# ISL6236A_DEMO.net
KiCad netlist of a schematic drawn in Altium Designer
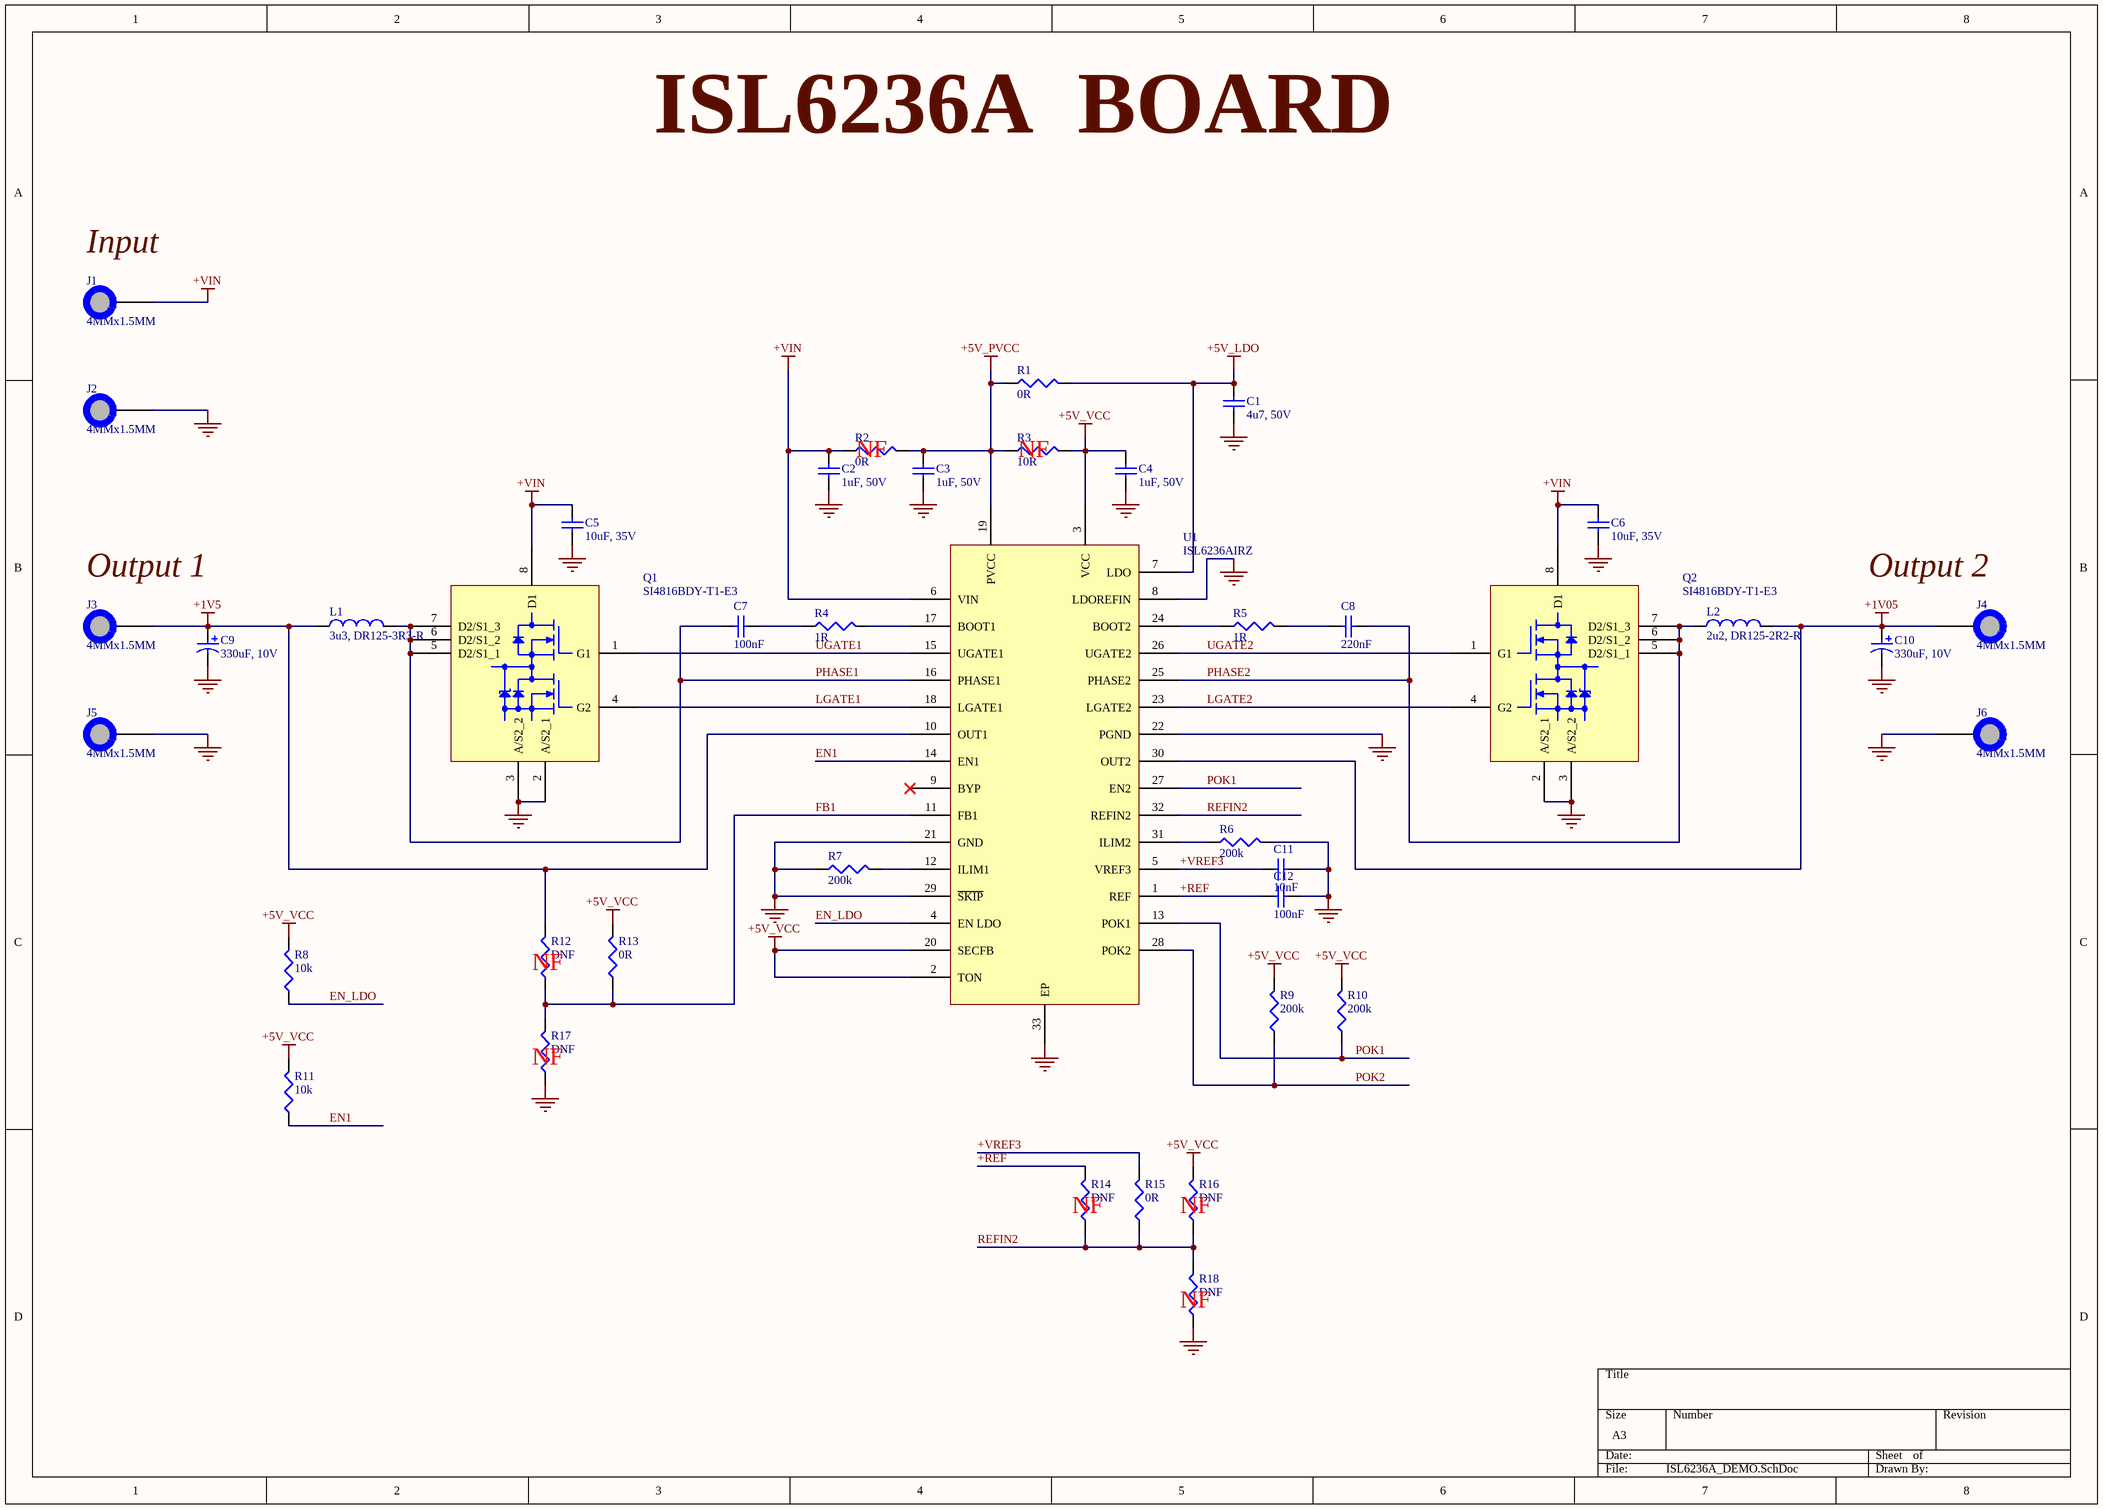
[diagram p0: ISL6236A_DEMO.SchDoc]

(export (version "E")
  (design (tool "Eeschema 10.0.6"))
  (components
    (comp (ref "C1")
      (value "4u7, 50V")
      (footprint "C1206")
      (description "CAP CER 4.7UF 50V X5R 1206")
      (fields
        (field (name "MANUFACTURER") "TDK")
        (field (name "MANUFACTURER PART NUMBER") "C3216X5R1H475K160AB")
      )
      (libsource (lib "ISL6236A_DEMO") (part "C3216X5R1H475K160AB"))
    )
    (comp (ref "C2")
      (value "1uF, 50V")
      (footprint "C0805")
      (description "Multilayer Ceramic Capacitors MLCC - SMD/SMT 1uF 50 Volts 10% X7R")
      (fields
        (field (name "MANUFACTURER") "KEMET")
        (field (name "MANUFACTURER PART NUMBER") "C0805C105K5RACTU")
      )
      (libsource (lib "ISL6236A_DEMO") (part "C0805C105K5RACTU"))
    )
    (comp (ref "C3")
      (value "1uF, 50V")
      (footprint "C0805")
      (description "Multilayer Ceramic Capacitors MLCC - SMD/SMT 1uF 50 Volts 10% X7R")
      (fields
        (field (name "MANUFACTURER") "KEMET")
        (field (name "MANUFACTURER PART NUMBER") "C0805C105K5RACTU")
      )
      (libsource (lib "ISL6236A_DEMO") (part "C0805C105K5RACTU"))
    )
    (comp (ref "C4")
      (value "1uF, 50V")
      (footprint "C0805")
      (description "Multilayer Ceramic Capacitors MLCC - SMD/SMT 1uF 50 Volts 10% X7R")
      (fields
        (field (name "MANUFACTURER") "KEMET")
        (field (name "MANUFACTURER PART NUMBER") "C0805C105K5RACTU")
      )
      (libsource (lib "ISL6236A_DEMO") (part "C0805C105K5RACTU"))
    )
    (comp (ref "C5")
      (value "10uF, 35V")
      (footprint "C1210")
      (description "1210 C 10uF Ceramic Multilayer Capacitor,  35 VDC,  +85degC,  X5R Dielec,  +/-10%")
      (fields
        (field (name "MANUFACTURER") "KEMET")
        (field (name "MANUFACTURER PART NUMBER") "C1210C106K6PACTU")
      )
      (libsource (lib "ISL6236A_DEMO") (part "C1210C106K6PACTU"))
    )
    (comp (ref "C6")
      (value "10uF, 35V")
      (footprint "C1210")
      (description "1210 C 10uF Ceramic Multilayer Capacitor,  35 VDC,  +85degC,  X5R Dielec,  +/-10%")
      (fields
        (field (name "MANUFACTURER") "KEMET")
        (field (name "MANUFACTURER PART NUMBER") "C1210C106K6PACTU")
      )
      (libsource (lib "ISL6236A_DEMO") (part "C1210C106K6PACTU"))
    )
    (comp (ref "C7")
      (value "100nF")
      (footprint "C0805")
      (description "Multilayer Ceramic Capacitors MLCC - SMD/SMT 50volts 0.1uF X7R 10%")
      (fields
        (field (name "MANUFACTURER") "KEMET")
        (field (name "MANUFACTURER PART NUMBER") "C0805C104K5RAC7800")
      )
      (libsource (lib "ISL6236A_DEMO") (part "C0805C104K5RAC7800"))
    )
    (comp (ref "C8")
      (value "220nF")
      (footprint "C0805")
      (description "CAP CER 0.22UF 50V X7R 0805")
      (fields
        (field (name "MANUFACTURER") "KEMET")
        (field (name "MANUFACTURER PART NUMBER") "C0805C224K5RACTU")
      )
      (libsource (lib "ISL6236A_DEMO") (part "C0805C224K5RACTU"))
    )
    (comp (ref "C9")
      (value "330uF, 10V")
      (footprint "7343-43")
      (description "Tantalum Capacitors - Polymer SMD 330uF 10volts 20%")
      (fields
        (field (name "MANUFACTURER") "KEMET")
        (field (name "MANUFACTURER PART NUMBER") "T530X337M010ATE004")
      )
      (libsource (lib "ISL6236A_DEMO") (part "T530X337M010ATE004"))
    )
    (comp (ref "C10")
      (value "330uF, 10V")
      (footprint "7343-43")
      (description "Tantalum Capacitors - Polymer SMD 330uF 10volts 20%")
      (fields
        (field (name "MANUFACTURER") "KEMET")
        (field (name "MANUFACTURER PART NUMBER") "T530X337M010ATE004")
      )
      (libsource (lib "ISL6236A_DEMO") (part "T530X337M010ATE004"))
    )
    (comp (ref "C11")
      (value "10nF")
      (footprint "C0805")
      (description "CAP CER 10000PF 50V X7R 0805")
      (fields
        (field (name "MANUFACTURER") "KEMET")
        (field (name "MANUFACTURER PART NUMBER") "C0805F103K5RACTU")
      )
      (libsource (lib "ISL6236A_DEMO") (part "C0805F103K5RACTU"))
    )
    (comp (ref "C12")
      (value "100nF")
      (footprint "C0805")
      (description "Multilayer Ceramic Capacitors MLCC - SMD/SMT 50volts 0.1uF X7R 10%")
      (fields
        (field (name "MANUFACTURER") "KEMET")
        (field (name "MANUFACTURER PART NUMBER") "C0805C104K5RAC7800")
      )
      (libsource (lib "ISL6236A_DEMO") (part "C0805C104K5RAC7800"))
    )
    (comp (ref "J1")
      (value "4MMx1.5MM")
      (footprint "PAD_WITH_HOLE_4MMx1MM5")
      (description "Pad with a hole 4mm x 1.5mm")
      (libsource (lib "ISL6236A_DEMO") (part "PAD_WITH_HOLE_4MMx1MM5"))
    )
    (comp (ref "J2")
      (value "4MMx1.5MM")
      (footprint "PAD_WITH_HOLE_4MMx1MM5")
      (description "Pad with a hole 4mm x 1.5mm")
      (libsource (lib "ISL6236A_DEMO") (part "PAD_WITH_HOLE_4MMx1MM5"))
    )
    (comp (ref "J3")
      (value "4MMx1.5MM")
      (footprint "PAD_WITH_HOLE_4MMx1MM5")
      (description "Pad with a hole 4mm x 1.5mm")
      (libsource (lib "ISL6236A_DEMO") (part "PAD_WITH_HOLE_4MMx1MM5"))
    )
    (comp (ref "J4")
      (value "4MMx1.5MM")
      (footprint "PAD_WITH_HOLE_4MMx1MM5")
      (description "Pad with a hole 4mm x 1.5mm")
      (libsource (lib "ISL6236A_DEMO") (part "PAD_WITH_HOLE_4MMx1MM5"))
    )
    (comp (ref "J5")
      (value "4MMx1.5MM")
      (footprint "PAD_WITH_HOLE_4MMx1MM5")
      (description "Pad with a hole 4mm x 1.5mm")
      (libsource (lib "ISL6236A_DEMO") (part "PAD_WITH_HOLE_4MMx1MM5"))
    )
    (comp (ref "J6")
      (value "4MMx1.5MM")
      (footprint "PAD_WITH_HOLE_4MMx1MM5")
      (description "Pad with a hole 4mm x 1.5mm")
      (libsource (lib "ISL6236A_DEMO") (part "PAD_WITH_HOLE_4MMx1MM5"))
    )
    (comp (ref "L1")
      (value "3u3, DR125-3R3-R")
      (footprint "DR125")
      (description "Inductor Power Shielded Drum Core 3.084uH/3.3uH 20% 100KHz Ferrite 9.26A 6.3mOhm DCR T/R")
      (fields
        (field (name "MANUFACTURER") "Eaton Cooper")
        (field (name "MANUFACTURER PART NUMBER") "DR125-3R3-R")
      )
      (libsource (lib "ISL6236A_DEMO") (part "DR125-3R3-R"))
    )
    (comp (ref "L2")
      (value "2u2, DR125-2R2-R")
      (footprint "DR125")
      (description "Fixed Inductors 2.2uH 15A 0.0045ohms")
      (fields
        (field (name "MANUFACTURER") "Eaton Cooper")
        (field (name "MANUFACTURER PART NUMBER") "DR125-2R2-R")
      )
      (libsource (lib "ISL6236A_DEMO") (part "DR125-2R2-R"))
    )
    (comp (ref "Q1")
      (value "SI4816BDY-T1-E3")
      (footprint "SO-8")
      (description "MOSFET 2N-CH 30V 5.8A 8-SOIC")
      (fields (field (name "MANUFACTURER") "Vishay Siliconix"))
      (libsource (lib "ISL6236A_DEMO") (part "SI4816BDY-T1-E3"))
    )
    (comp (ref "Q2")
      (value "SI4816BDY-T1-E3")
      (footprint "SO-8")
      (description "MOSFET 2N-CH 30V 5.8A 8-SOIC")
      (fields (field (name "MANUFACTURER") "Vishay Siliconix"))
      (libsource (lib "") (part "SI4816BDY-T1-E3_1"))
    )
    (comp (ref "R1")
      (value "0R")
      (footprint "R0805")
      (description "Thick Film Resistors - SMD 1/8W 0.0ohm 5%")
      (fields
        (field (name "MANUFACTURER") "Yageo")
        (field (name "MANUFACTURER PART NUMBER") "AC0805JR-070RL")
      )
      (libsource (lib "ISL6236A_DEMO") (part "AC0805JR-070RL"))
    )
    (comp (ref "R2")
      (value "0R")
      (footprint "R0805")
      (description "Thick Film Resistors - SMD 1/8W 0.0ohm 5%")
      (fields
        (field (name "MANUFACTURER") "Yageo")
        (field (name "MANUFACTURER PART NUMBER") "AC0805JR-070RL")
      )
      (libsource (lib "ISL6236A_DEMO") (part "AC0805JR-070RL"))
    )
    (comp (ref "R3")
      (value "10R")
      (footprint "R0805")
      (description "Thick Film Resistors - SMD 1/8W 10ohm 1%")
      (fields
        (field (name "MANUFACTURER") "Yageo")
        (field (name "MANUFACTURER PART NUMBER") "AC0805FR-0710RL")
      )
      (libsource (lib "ISL6236A_DEMO") (part "AC0805FR-0710RL"))
    )
    (comp (ref "R4")
      (value "1R")
      (footprint "R0805")
      (description "Thick Film Resistors - SMD 1/8W 1ohm 1% AEC-Q200")
      (fields
        (field (name "MANUFACTURER") "Yageo")
        (field (name "MANUFACTURER PART NUMBER") "AC0805FR-071RL")
      )
      (libsource (lib "ISL6236A_DEMO") (part "AC0805FR-071RL"))
    )
    (comp (ref "R5")
      (value "1R")
      (footprint "R0805")
      (description "Thick Film Resistors - SMD 1/8W 1ohm 1% AEC-Q200")
      (fields
        (field (name "MANUFACTURER") "Yageo")
        (field (name "MANUFACTURER PART NUMBER") "AC0805FR-071RL")
      )
      (libsource (lib "ISL6236A_DEMO") (part "AC0805FR-071RL"))
    )
    (comp (ref "R6")
      (value "200k")
      (footprint "R0805")
      (description "Thick Film Resistors - SMD 1/8W 200K ohm 1%")
      (fields
        (field (name "MANUFACTURER") "Yageo")
        (field (name "MANUFACTURER PART NUMBER") "AC0805FR-07200KL")
      )
      (libsource (lib "ISL6236A_DEMO") (part "AC0805FR-07200KL"))
    )
    (comp (ref "R7")
      (value "200k")
      (footprint "R0805")
      (description "Thick Film Resistors - SMD 1/8W 200K ohm 1%")
      (fields
        (field (name "MANUFACTURER") "Yageo")
        (field (name "MANUFACTURER PART NUMBER") "AC0805FR-07200KL")
      )
      (libsource (lib "ISL6236A_DEMO") (part "AC0805FR-07200KL"))
    )
    (comp (ref "R8")
      (value "10k")
      (footprint "R0805")
      (description "RES SMD 10K OHM 1% 1/8W 0805")
      (fields
        (field (name "MANUFACTURER") "Yageo")
        (field (name "MANUFACTURER PART NUMBER") "AC0805FR-0710KL")
      )
      (libsource (lib "ISL6236A_DEMO") (part "AC0805FR-0710KL"))
    )
    (comp (ref "R9")
      (value "200k")
      (footprint "R0805")
      (description "Thick Film Resistors - SMD 1/8W 200K ohm 1%")
      (fields
        (field (name "MANUFACTURER") "Yageo")
        (field (name "MANUFACTURER PART NUMBER") "AC0805FR-07200KL")
      )
      (libsource (lib "ISL6236A_DEMO") (part "AC0805FR-07200KL"))
    )
    (comp (ref "R10")
      (value "200k")
      (footprint "R0805")
      (description "Thick Film Resistors - SMD 1/8W 200K ohm 1%")
      (fields
        (field (name "MANUFACTURER") "Yageo")
        (field (name "MANUFACTURER PART NUMBER") "AC0805FR-07200KL")
      )
      (libsource (lib "ISL6236A_DEMO") (part "AC0805FR-07200KL"))
    )
    (comp (ref "R11")
      (value "10k")
      (footprint "R0805")
      (description "RES SMD 10K OHM 1% 1/8W 0805")
      (fields
        (field (name "MANUFACTURER") "Yageo")
        (field (name "MANUFACTURER PART NUMBER") "AC0805FR-0710KL")
      )
      (libsource (lib "ISL6236A_DEMO") (part "AC0805FR-0710KL"))
    )
    (comp (ref "R12") (value "DNF") (footprint "R0805") (libsource (lib "ISL6236A_DEMO") (part "RES")))
    (comp (ref "R13")
      (value "0R")
      (footprint "R0805")
      (description "Thick Film Resistors - SMD 1/8W 0.0ohm 5%")
      (fields
        (field (name "MANUFACTURER") "Yageo")
        (field (name "MANUFACTURER PART NUMBER") "AC0805JR-070RL")
      )
      (libsource (lib "ISL6236A_DEMO") (part "AC0805JR-070RL"))
    )
    (comp (ref "R14") (value "DNF") (footprint "R0805") (libsource (lib "ISL6236A_DEMO") (part "RES")))
    (comp (ref "R15")
      (value "0R")
      (footprint "R0805")
      (description "Thick Film Resistors - SMD 1/8W 0.0ohm 5%")
      (fields
        (field (name "MANUFACTURER") "Yageo")
        (field (name "MANUFACTURER PART NUMBER") "AC0805JR-070RL")
      )
      (libsource (lib "ISL6236A_DEMO") (part "AC0805JR-070RL"))
    )
    (comp (ref "R16") (value "DNF") (footprint "R0805") (libsource (lib "ISL6236A_DEMO") (part "RES")))
    (comp (ref "R17") (value "DNF") (footprint "R0805") (libsource (lib "ISL6236A_DEMO") (part "RES")))
    (comp (ref "R18") (value "DNF") (footprint "R0805") (libsource (lib "ISL6236A_DEMO") (part "RES")))
    (comp (ref "U1")
      (value "ISL6236AIRZ")
      (footprint "L32.5x5B")
      (description "IC MAIN PWR CTRLR QUAD 32-QFN")
      (fields (field (name "MANUFACTURER") "Intersil"))
      (libsource (lib "ISL6236A_DEMO") (part "ISL6236AIRZ"))
    )
  )
  (nets
    (net (code "1") (name "+1V5") (class "Default")
      (node (ref "C9") (pin "1") (pinfunction "1_1") (pintype "passive"))
      (node (ref "J3") (pin "1") (pinfunction "1_1") (pintype "passive"))
      (node (ref "L1") (pin "1") (pinfunction "1_1") (pintype "passive"))
      (node (ref "R12") (pin "2") (pinfunction "2_2") (pintype "passive"))
      (node (ref "U1") (pin "10") (pinfunction "OUT1_10") (pintype "passive"))
    )
    (net (code "2") (name "+1V05") (class "Default")
      (node (ref "C10") (pin "1") (pinfunction "1_1") (pintype "passive"))
      (node (ref "J4") (pin "1") (pinfunction "1_1") (pintype "passive"))
      (node (ref "L2") (pin "2") (pinfunction "2_2") (pintype "passive"))
      (node (ref "U1") (pin "30") (pinfunction "OUT2_30") (pintype "passive"))
    )
    (net (code "3") (name "+5V_LDO") (class "Default")
      (node (ref "C1") (pin "2") (pinfunction "2_2") (pintype "passive"))
      (node (ref "R1") (pin "2") (pinfunction "2_2") (pintype "passive"))
      (node (ref "U1") (pin "7") (pinfunction "LDO_7") (pintype "passive"))
    )
    (net (code "4") (name "+5V_PVCC") (class "Default")
      (node (ref "C3") (pin "2") (pinfunction "2_2") (pintype "passive"))
      (node (ref "R1") (pin "1") (pinfunction "1_1") (pintype "passive"))
      (node (ref "R2") (pin "2") (pinfunction "2_2") (pintype "passive"))
      (node (ref "R3") (pin "1") (pinfunction "1_1") (pintype "passive"))
      (node (ref "U1") (pin "19") (pinfunction "PVCC_19") (pintype "passive"))
    )
    (net (code "5") (name "+5V_VCC") (class "Default")
      (node (ref "C4") (pin "2") (pinfunction "2_2") (pintype "passive"))
      (node (ref "R10") (pin "2") (pinfunction "2_2") (pintype "passive"))
      (node (ref "R11") (pin "2") (pinfunction "2_2") (pintype "passive"))
      (node (ref "R13") (pin "2") (pinfunction "2_2") (pintype "passive"))
      (node (ref "R16") (pin "2") (pinfunction "2_2") (pintype "passive"))
      (node (ref "R3") (pin "2") (pinfunction "2_2") (pintype "passive"))
      (node (ref "R8") (pin "2") (pinfunction "2_2") (pintype "passive"))
      (node (ref "R9") (pin "2") (pinfunction "2_2") (pintype "passive"))
      (node (ref "U1") (pin "2") (pinfunction "TON_2") (pintype "passive"))
      (node (ref "U1") (pin "20") (pinfunction "SECFB_20") (pintype "passive"))
      (node (ref "U1") (pin "3") (pinfunction "VCC_3") (pintype "passive"))
    )
    (net (code "6") (name "+VIN") (class "Default")
      (node (ref "C2") (pin "2") (pinfunction "2_2") (pintype "passive"))
      (node (ref "C5") (pin "2") (pinfunction "2_2") (pintype "passive"))
      (node (ref "C6") (pin "2") (pinfunction "2_2") (pintype "passive"))
      (node (ref "J1") (pin "1") (pinfunction "1_1") (pintype "passive"))
      (node (ref "Q1") (pin "8") (pinfunction "D1_8") (pintype "passive"))
      (node (ref "Q2") (pin "8") (pinfunction "D1_8") (pintype "passive"))
      (node (ref "R2") (pin "1") (pinfunction "1_1") (pintype "passive"))
      (node (ref "U1") (pin "6") (pinfunction "VIN_6") (pintype "passive"))
    )
    (net (code "7") (name "/+REF") (class "Default")
      (node (ref "C12") (pin "1") (pinfunction "1_1") (pintype "passive"))
      (node (ref "R14") (pin "2") (pinfunction "2_2") (pintype "passive"))
      (node (ref "U1") (pin "1") (pinfunction "REF_1") (pintype "passive"))
    )
    (net (code "8") (name "/+VREF3") (class "Default")
      (node (ref "C11") (pin "1") (pinfunction "1_1") (pintype "passive"))
      (node (ref "R15") (pin "2") (pinfunction "2_2") (pintype "passive"))
      (node (ref "U1") (pin "5") (pinfunction "VREF3_5") (pintype "passive"))
    )
    (net (code "9") (name "/EN1") (class "Default")
      (node (ref "R11") (pin "1") (pinfunction "1_1") (pintype "passive"))
      (node (ref "U1") (pin "14") (pinfunction "EN1_14") (pintype "passive"))
    )
    (net (code "10") (name "/EN_LDO") (class "Default")
      (node (ref "R8") (pin "1") (pinfunction "1_1") (pintype "passive"))
      (node (ref "U1") (pin "4") (pinfunction "EN_LDO_4") (pintype "passive"))
    )
    (net (code "11") (name "/FB1") (class "Default")
      (node (ref "R12") (pin "1") (pinfunction "1_1") (pintype "passive"))
      (node (ref "R13") (pin "1") (pinfunction "1_1") (pintype "passive"))
      (node (ref "R17") (pin "2") (pinfunction "2_2") (pintype "passive"))
      (node (ref "U1") (pin "11") (pinfunction "FB1_11") (pintype "passive"))
    )
    (net (code "12") (name "/LGATE1") (class "Default")
      (node (ref "Q1") (pin "4") (pinfunction "G2_4") (pintype "passive"))
      (node (ref "U1") (pin "18") (pinfunction "LGATE1_18") (pintype "passive"))
    )
    (net (code "13") (name "/LGATE2") (class "Default")
      (node (ref "Q2") (pin "4") (pinfunction "G2_4") (pintype "passive"))
      (node (ref "U1") (pin "23") (pinfunction "LGATE2_23") (pintype "passive"))
    )
    (net (code "14") (name "/PHASE1") (class "Default")
      (node (ref "C7") (pin "1") (pinfunction "1_1") (pintype "passive"))
      (node (ref "L1") (pin "2") (pinfunction "2_2") (pintype "passive"))
      (node (ref "Q1") (pin "5") (pinfunction "D2/S1_1_5") (pintype "passive"))
      (node (ref "Q1") (pin "6") (pinfunction "D2/S1_2_6") (pintype "passive"))
      (node (ref "Q1") (pin "7") (pinfunction "D2/S1_3_7") (pintype "passive"))
      (node (ref "U1") (pin "16") (pinfunction "PHASE1_16") (pintype "passive"))
    )
    (net (code "15") (name "/PHASE2") (class "Default")
      (node (ref "C8") (pin "2") (pinfunction "2_2") (pintype "passive"))
      (node (ref "L2") (pin "1") (pinfunction "1_1") (pintype "passive"))
      (node (ref "Q2") (pin "5") (pinfunction "D2/S1_1_5") (pintype "passive"))
      (node (ref "Q2") (pin "6") (pinfunction "D2/S1_2_6") (pintype "passive"))
      (node (ref "Q2") (pin "7") (pinfunction "D2/S1_3_7") (pintype "passive"))
      (node (ref "U1") (pin "25") (pinfunction "PHASE2_25") (pintype "passive"))
    )
    (net (code "16") (name "/POK1") (class "Default")
      (node (ref "R10") (pin "1") (pinfunction "1_1") (pintype "passive"))
      (node (ref "U1") (pin "13") (pinfunction "POK1_13") (pintype "passive"))
      (node (ref "U1") (pin "27") (pinfunction "EN2_27") (pintype "passive"))
    )
    (net (code "17") (name "/POK2") (class "Default")
      (node (ref "R9") (pin "1") (pinfunction "1_1") (pintype "passive"))
      (node (ref "U1") (pin "28") (pinfunction "POK2_28") (pintype "passive"))
    )
    (net (code "18") (name "/REFIN2") (class "Default")
      (node (ref "R14") (pin "1") (pinfunction "1_1") (pintype "passive"))
      (node (ref "R15") (pin "1") (pinfunction "1_1") (pintype "passive"))
      (node (ref "R16") (pin "1") (pinfunction "1_1") (pintype "passive"))
      (node (ref "R18") (pin "2") (pinfunction "2_2") (pintype "passive"))
      (node (ref "U1") (pin "32") (pinfunction "REFIN2_32") (pintype "passive"))
    )
    (net (code "19") (name "/UGATE1") (class "Default")
      (node (ref "Q1") (pin "1") (pinfunction "G1_1") (pintype "passive"))
      (node (ref "U1") (pin "15") (pinfunction "UGATE1_15") (pintype "passive"))
    )
    (net (code "20") (name "/UGATE2") (class "Default")
      (node (ref "Q2") (pin "1") (pinfunction "G1_1") (pintype "passive"))
      (node (ref "U1") (pin "26") (pinfunction "UGATE2_26") (pintype "passive"))
    )
    (net (code "21") (name "GND") (class "Default")
      (node (ref "C1") (pin "1") (pinfunction "1_1") (pintype "passive"))
      (node (ref "C10") (pin "2") (pinfunction "2_2") (pintype "passive"))
      (node (ref "C11") (pin "2") (pinfunction "2_2") (pintype "passive"))
      (node (ref "C12") (pin "2") (pinfunction "2_2") (pintype "passive"))
      (node (ref "C2") (pin "1") (pinfunction "1_1") (pintype "passive"))
      (node (ref "C3") (pin "1") (pinfunction "1_1") (pintype "passive"))
      (node (ref "C4") (pin "1") (pinfunction "1_1") (pintype "passive"))
      (node (ref "C5") (pin "1") (pinfunction "1_1") (pintype "passive"))
      (node (ref "C6") (pin "1") (pinfunction "1_1") (pintype "passive"))
      (node (ref "C9") (pin "2") (pinfunction "2_2") (pintype "passive"))
      (node (ref "J2") (pin "1") (pinfunction "1_1") (pintype "passive"))
      (node (ref "J5") (pin "1") (pinfunction "1_1") (pintype "passive"))
      (node (ref "J6") (pin "1") (pinfunction "1_1") (pintype "passive"))
      (node (ref "Q1") (pin "2") (pinfunction "A/S2_1_2") (pintype "passive"))
      (node (ref "Q1") (pin "3") (pinfunction "A/S2_2_3") (pintype "passive"))
      (node (ref "Q2") (pin "2") (pinfunction "A/S2_1_2") (pintype "passive"))
      (node (ref "Q2") (pin "3") (pinfunction "A/S2_2_3") (pintype "passive"))
      (node (ref "R17") (pin "1") (pinfunction "1_1") (pintype "passive"))
      (node (ref "R18") (pin "1") (pinfunction "1_1") (pintype "passive"))
      (node (ref "R6") (pin "2") (pinfunction "2_2") (pintype "passive"))
      (node (ref "R7") (pin "1") (pinfunction "1_1") (pintype "passive"))
      (node (ref "U1") (pin "21") (pinfunction "GND_21") (pintype "passive"))
      (node (ref "U1") (pin "22") (pinfunction "PGND_22") (pintype "passive"))
      (node (ref "U1") (pin "29") (pinfunction "~{SKIP}_29") (pintype "passive"))
      (node (ref "U1") (pin "33") (pinfunction "EP_33") (pintype "passive"))
      (node (ref "U1") (pin "8") (pinfunction "LDOREFIN_8") (pintype "passive"))
    )
    (net (code "22") (name "Net-(C7-Pad2)") (class "Default")
      (node (ref "C7") (pin "2") (pinfunction "2_2") (pintype "passive"))
      (node (ref "R4") (pin "1") (pinfunction "1_1") (pintype "passive"))
    )
    (net (code "23") (name "Net-(C8-Pad1)") (class "Default")
      (node (ref "C8") (pin "1") (pinfunction "1_1") (pintype "passive"))
      (node (ref "R5") (pin "2") (pinfunction "2_2") (pintype "passive"))
    )
    (net (code "24") (name "Net-(U1-BOOT1)") (class "Default")
      (node (ref "R4") (pin "2") (pinfunction "2_2") (pintype "passive"))
      (node (ref "U1") (pin "17") (pinfunction "BOOT1_17") (pintype "passive"))
    )
    (net (code "25") (name "Net-(U1-BOOT2)") (class "Default")
      (node (ref "R5") (pin "1") (pinfunction "1_1") (pintype "passive"))
      (node (ref "U1") (pin "24") (pinfunction "BOOT2_24") (pintype "passive"))
    )
    (net (code "26") (name "Net-(U1-ILIM1)") (class "Default")
      (node (ref "R7") (pin "2") (pinfunction "2_2") (pintype "passive"))
      (node (ref "U1") (pin "12") (pinfunction "ILIM1_12") (pintype "passive"))
    )
    (net (code "27") (name "Net-(U1-ILIM2)") (class "Default")
      (node (ref "R6") (pin "1") (pinfunction "1_1") (pintype "passive"))
      (node (ref "U1") (pin "31") (pinfunction "ILIM2_31") (pintype "passive"))
    )
    (net (code "28") (name "unconnected-(U1-BYP-Pad9)") (class "Default")
      (node (ref "U1") (pin "9") (pinfunction "BYP_9") (pintype "passive+no_connect"))
    )
  )
)
